# edison_mezzanine_pi_breakout.net
KiCad netlist of a schematic drawn in EAGLE
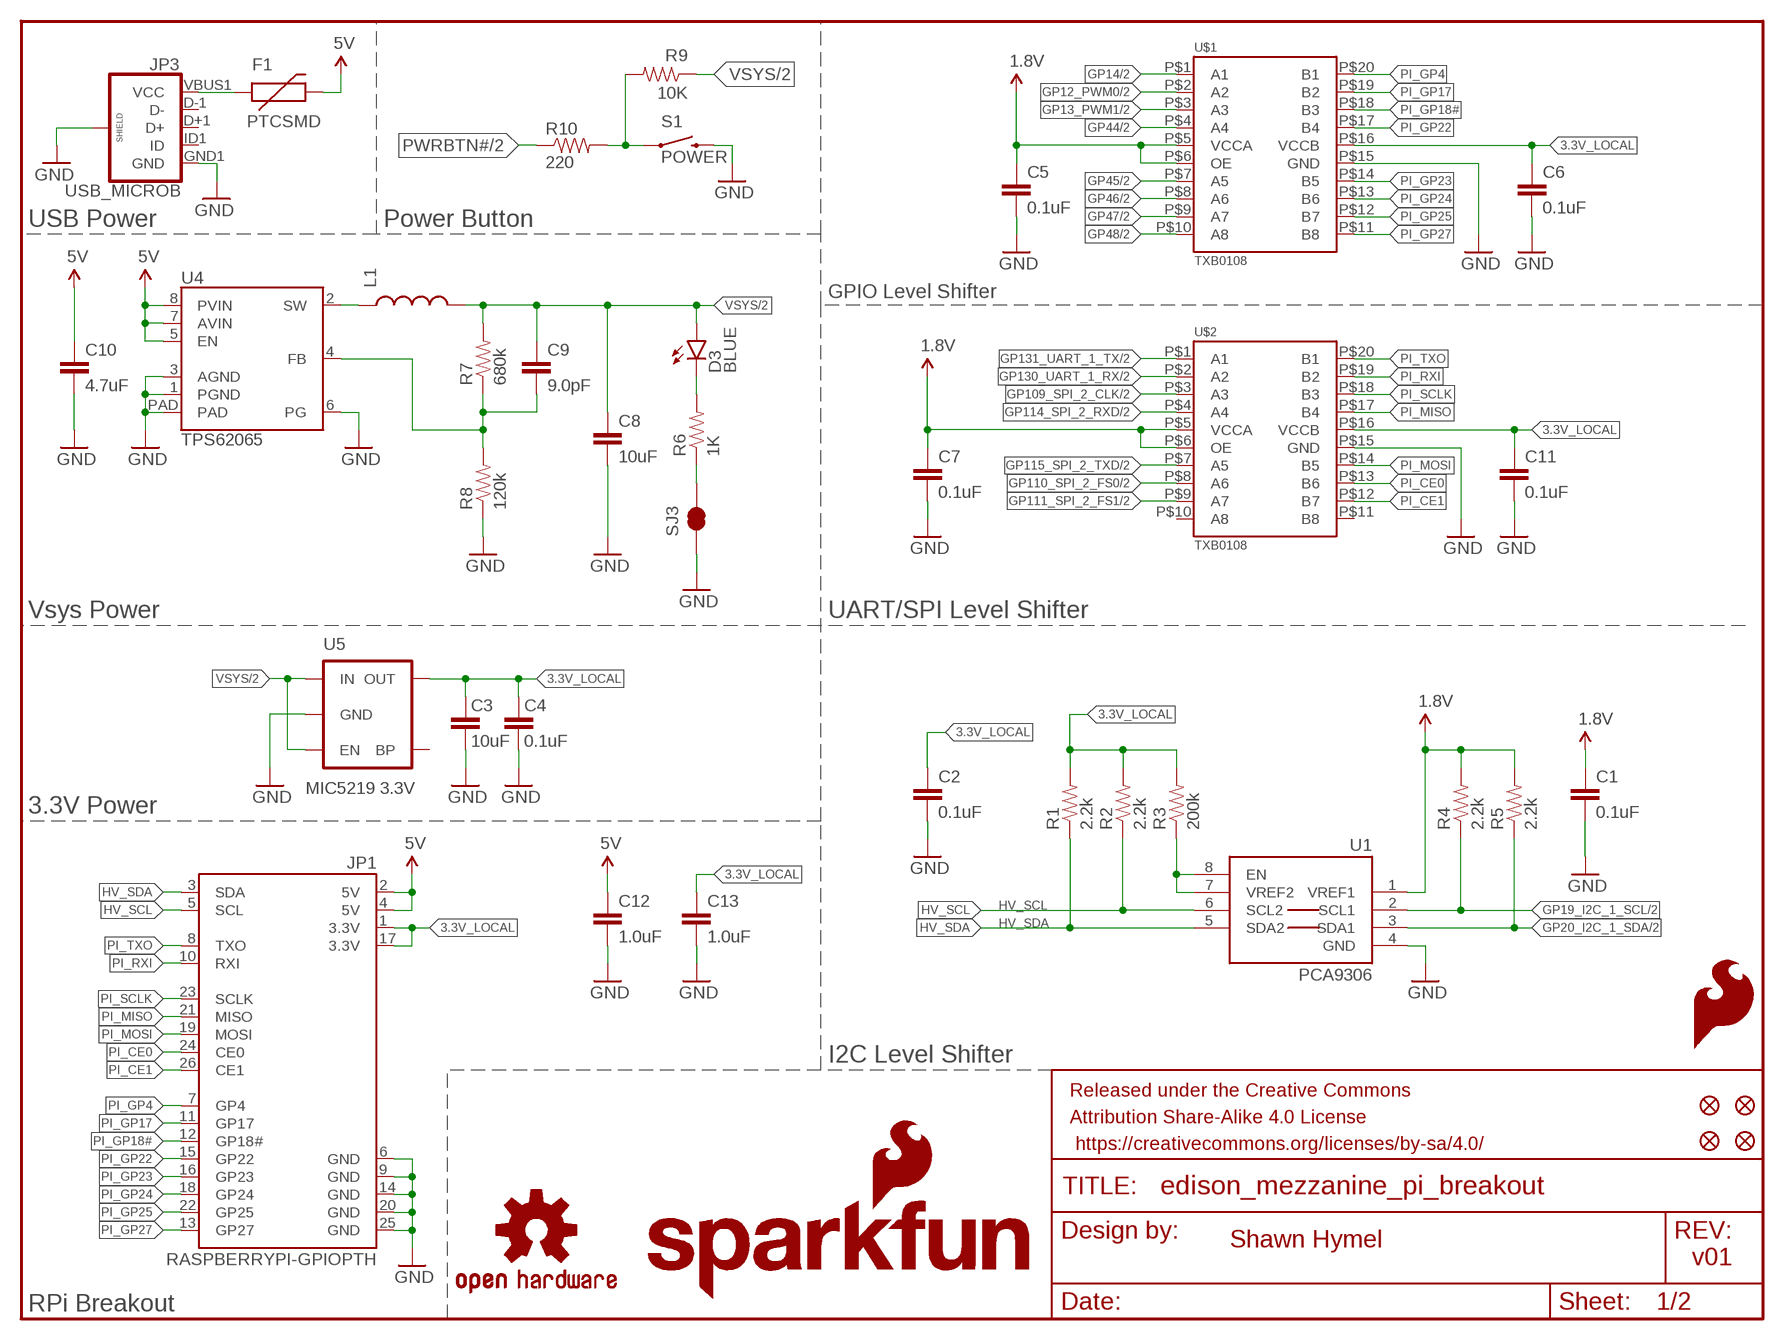
[diagram p0: schematic, sheet 1]
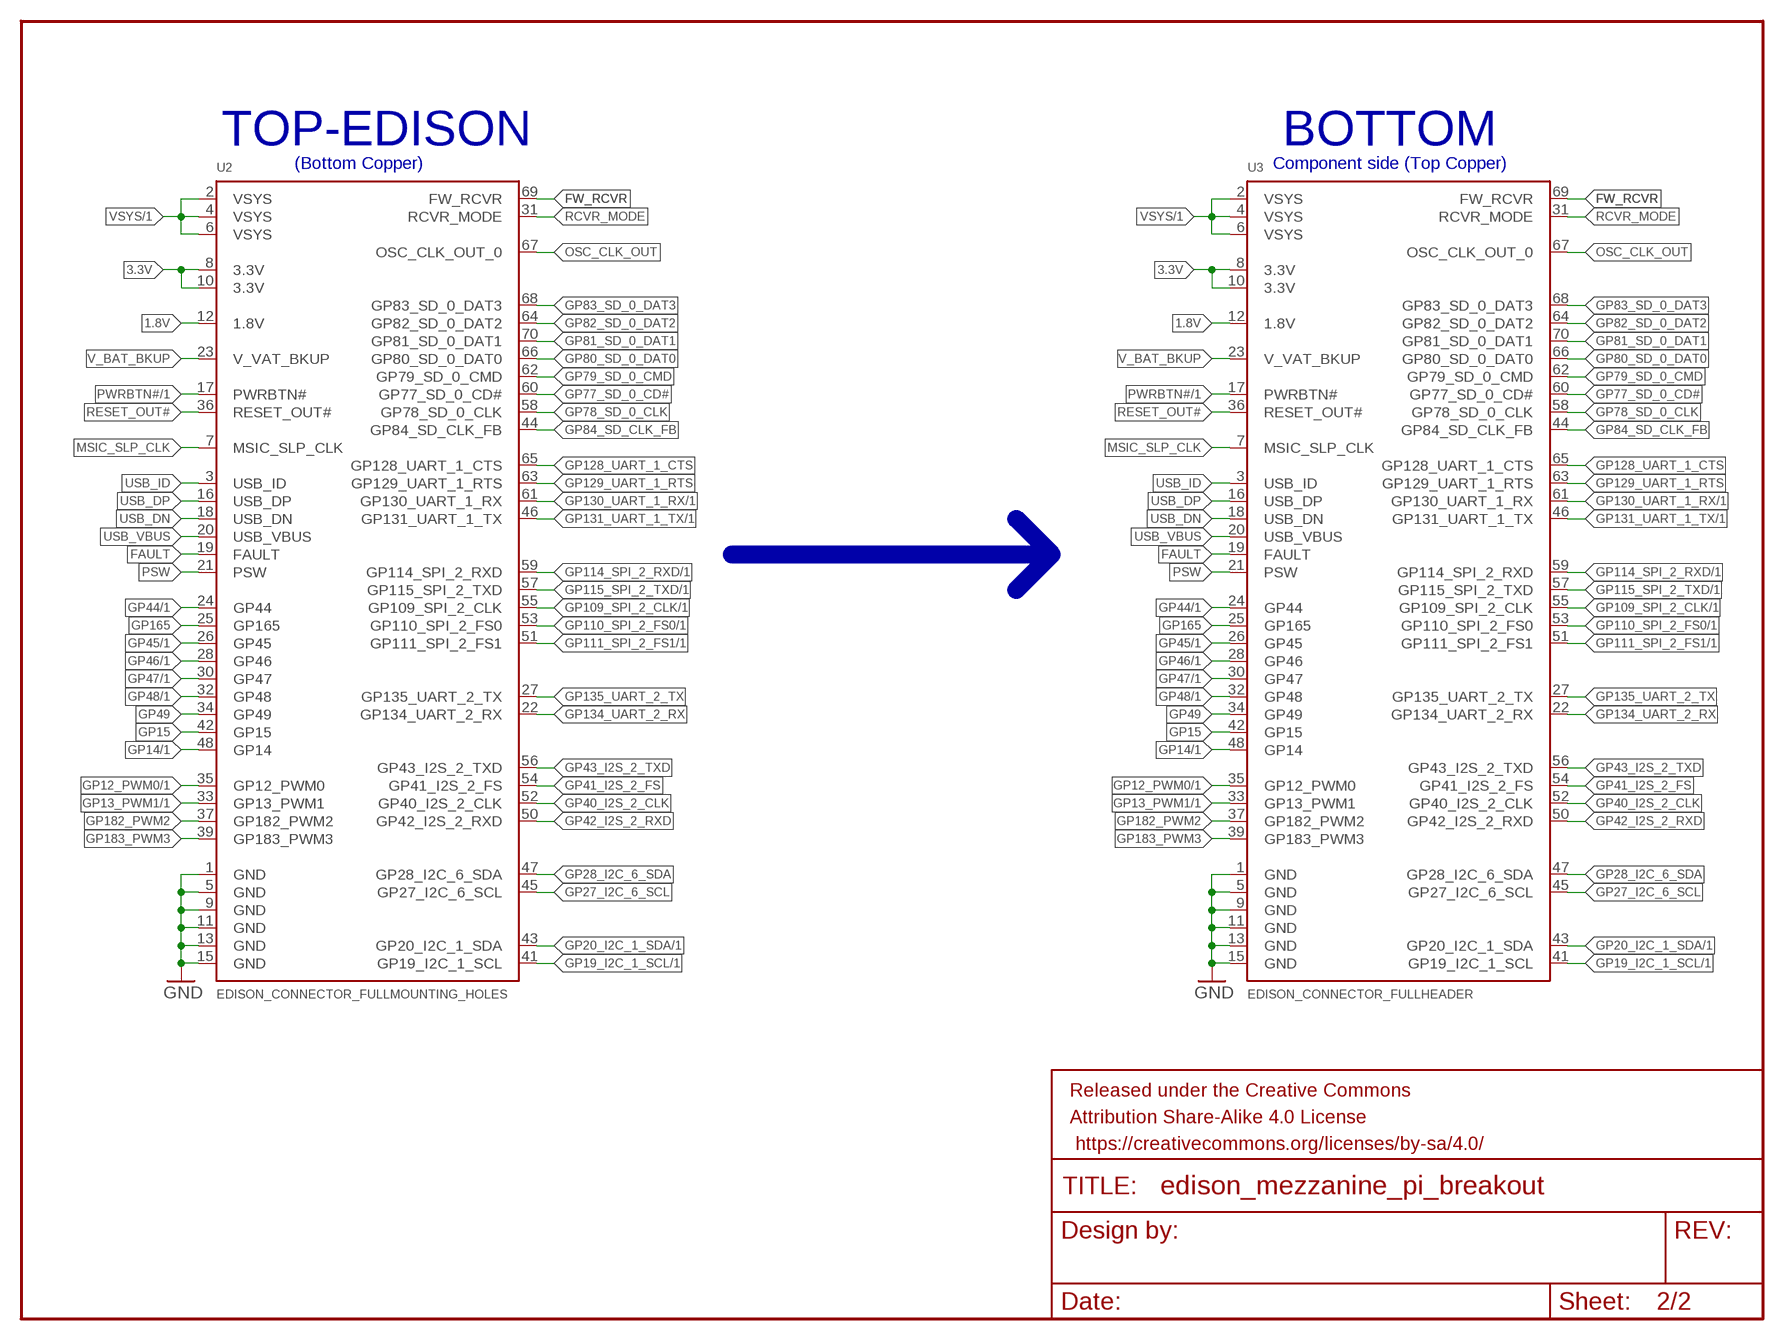
[diagram p1: schematic, sheet 2]

(export (version "E")
  (design (tool "Eeschema 10.0.6"))
  (components
    (comp (ref "FRAME2")
      (value "FRAME-LETTER")
      (footprint "eagle-import:CREATIVE_COMMONS")
      (libsource (lib "eagle-import") (part "FRAME-LETTER"))
    )
    (comp (ref "U2")
      (value "EDISON_CONNECTOR_FULLMOUNTING_HOLES")
      (footprint "eagle-import:EDISON_DAUGHTER")
      (libsource (lib "eagle-import") (part "EDISON_CONNECTOR_FULLMOUNTING_HOLES"))
    )
    (comp (ref "U3")
      (value "EDISON_CONNECTOR_FULLHEADER")
      (footprint "eagle-import:DF40C-70DP-0.4(51)")
      (libsource (lib "eagle-import") (part "EDISON_CONNECTOR_FULLHEADER"))
    )
    (comp (ref "C1")
      (value "0.1uF")
      (footprint "eagle-import:0603-CAP")
      (libsource (lib "eagle-import") (part "0.1UF-25V(+80/-20%)(0603)"))
    )
    (comp (ref "C2")
      (value "0.1uF")
      (footprint "eagle-import:0603-CAP")
      (libsource (lib "eagle-import") (part "0.1UF-25V(+80/-20%)(0603)"))
    )
    (comp (ref "C3")
      (value "10uF")
      (footprint "eagle-import:0805")
      (libsource (lib "eagle-import") (part "CAP0805"))
    )
    (comp (ref "C4")
      (value "0.1uF")
      (footprint "eagle-import:0603-CAP")
      (libsource (lib "eagle-import") (part "0.1UF-25V(+80/-20%)(0603)"))
    )
    (comp (ref "C5")
      (value "0.1uF")
      (footprint "eagle-import:0603-CAP")
      (libsource (lib "eagle-import") (part "0.1UF-25V(+80/-20%)(0603)"))
    )
    (comp (ref "C6")
      (value "0.1uF")
      (footprint "eagle-import:0603-CAP")
      (libsource (lib "eagle-import") (part "0.1UF-25V(+80/-20%)(0603)"))
    )
    (comp (ref "C7")
      (value "0.1uF")
      (footprint "eagle-import:0603-CAP")
      (libsource (lib "eagle-import") (part "0.1UF-25V(+80/-20%)(0603)"))
    )
    (comp (ref "C8")
      (value "10uF")
      (footprint "eagle-import:1206")
      (libsource (lib "eagle-import") (part "10UF-6.3V-20%(1206)"))
    )
    (comp (ref "C9")
      (value "9.0pF")
      (footprint "eagle-import:0603-CAP")
      (libsource (lib "eagle-import") (part "9.0PF-50V-10%(0603)"))
    )
    (comp (ref "C10")
      (value "4.7uF")
      (footprint "eagle-import:0603-CAP")
      (libsource (lib "eagle-import") (part "4.7UF-6.3V-10%(0603)0603"))
    )
    (comp (ref "C11")
      (value "0.1uF")
      (footprint "eagle-import:0603-CAP")
      (libsource (lib "eagle-import") (part "0.1UF-25V(+80/-20%)(0603)"))
    )
    (comp (ref "C12")
      (value "1.0uF")
      (footprint "eagle-import:0603-CAP")
      (libsource (lib "eagle-import") (part "1.0UF-16V-10%(0603)"))
    )
    (comp (ref "C13")
      (value "1.0uF")
      (footprint "eagle-import:0603-CAP")
      (libsource (lib "eagle-import") (part "1.0UF-16V-10%(0603)"))
    )
    (comp (ref "D3")
      (value "BLUE")
      (footprint "eagle-import:LED-0603")
      (libsource (lib "eagle-import") (part "LED-BLUE0603"))
    )
    (comp (ref "F1")
      (value "PTCSMD")
      (footprint "eagle-import:PTC-1206")
      (libsource (lib "eagle-import") (part "PTCSMD"))
    )
    (comp (ref "FID1")
      (value "FIDUCIAL1X2")
      (footprint "eagle-import:FIDUCIAL-1X2")
      (libsource (lib "eagle-import") (part "FIDUCIAL1X2"))
    )
    (comp (ref "FID2")
      (value "FIDUCIAL1X2")
      (footprint "eagle-import:FIDUCIAL-1X2")
      (libsource (lib "eagle-import") (part "FIDUCIAL1X2"))
    )
    (comp (ref "FID3")
      (value "FIDUCIAL1X2")
      (footprint "eagle-import:FIDUCIAL-1X2")
      (libsource (lib "eagle-import") (part "FIDUCIAL1X2"))
    )
    (comp (ref "FID4")
      (value "FIDUCIAL1X2")
      (footprint "eagle-import:FIDUCIAL-1X2")
      (libsource (lib "eagle-import") (part "FIDUCIAL1X2"))
    )
    (comp (ref "FRAME1")
      (value "FRAME-LETTER")
      (footprint "eagle-import:CREATIVE_COMMONS")
      (libsource (lib "eagle-import") (part "FRAME-LETTER"))
    )
    (comp (ref "JP1")
      (value "RASPBERRYPI-GPIOPTH")
      (footprint "eagle-import:2X13-SHROUDED")
      (libsource (lib "eagle-import") (part "RASPBERRYPI-GPIOPTH"))
    )
    (comp (ref "JP3")
      (value "USB_MICROB")
      (footprint "eagle-import:USB-B-MICRO-SMD_V03")
      (libsource (lib "eagle-import") (part "USB_MICROB_PLUGCONN-11752"))
    )
    (comp (ref "L1")
      (value "INDUCTOR")
      (footprint "eagle-import:INDUCTOR-SRP4020")
      (libsource (lib "eagle-import") (part "INDUCTOR"))
    )
    (comp (ref "LOGO1")
      (value "OSHW-LOGOS")
      (footprint "eagle-import:OSHW-LOGO-S")
      (libsource (lib "eagle-import") (part "OSHW-LOGOS"))
    )
    (comp (ref "LOGO3")
      (value "SFE_LOGO_FLAME.1_INCH")
      (footprint "eagle-import:SFE_LOGO_FLAME_.1")
      (libsource (lib "eagle-import") (part "SFE_LOGO_FLAME.1_INCH"))
    )
    (comp (ref "LOGO4")
      (value "SFE_LOGO_NAME_FLAME.1_INCH")
      (footprint "eagle-import:SFE_LOGO_NAME_FLAME_.1")
      (libsource (lib "eagle-import") (part "SFE_LOGO_NAME_FLAME.1_INCH"))
    )
    (comp (ref "R1")
      (value "2.2k")
      (footprint "eagle-import:0603-RES")
      (libsource (lib "eagle-import") (part "2.2KOHM1/10W1%(0603)"))
    )
    (comp (ref "R2")
      (value "2.2k")
      (footprint "eagle-import:0603-RES")
      (libsource (lib "eagle-import") (part "2.2KOHM1/10W1%(0603)"))
    )
    (comp (ref "R3")
      (value "200k")
      (footprint "eagle-import:0603-RES")
      (libsource (lib "eagle-import") (part "200KOHM1/10W1%(0603)200K"))
    )
    (comp (ref "R4")
      (value "2.2k")
      (footprint "eagle-import:0603-RES")
      (libsource (lib "eagle-import") (part "2.2KOHM1/10W1%(0603)"))
    )
    (comp (ref "R5")
      (value "2.2k")
      (footprint "eagle-import:0603-RES")
      (libsource (lib "eagle-import") (part "2.2KOHM1/10W1%(0603)"))
    )
    (comp (ref "R6")
      (value "1K")
      (footprint "eagle-import:0603-RES")
      (libsource (lib "eagle-import") (part "1KOHM1/10W1%(0603)"))
    )
    (comp (ref "R7")
      (value "680k")
      (footprint "eagle-import:0603-RES")
      (libsource (lib "eagle-import") (part "RESISTOR0603"))
    )
    (comp (ref "R8")
      (value "120k")
      (footprint "eagle-import:0603-RES")
      (libsource (lib "eagle-import") (part "RESISTOR0603"))
    )
    (comp (ref "R9")
      (value "10K")
      (footprint "eagle-import:0603-RES")
      (libsource (lib "eagle-import") (part "10KOHM1/10W1%(0603)0603"))
    )
    (comp (ref "R10")
      (value "220")
      (footprint "eagle-import:0603-RES")
      (libsource (lib "eagle-import") (part "RESISTOR0603"))
    )
    (comp (ref "S1")
      (value "POWER")
      (footprint "eagle-import:TACTILE-SWITCH-1101NE")
      (libsource (lib "eagle-import") (part "SWITCH-MOMENTARY-2-SMD-1101NE"))
    )
    (comp (ref "SJ3")
      (value "JUMPER-PAD-2-NC_BY_TRACE")
      (footprint "eagle-import:PAD-JUMPER-2-NC_BY_TRACE_YES_SILK")
      (libsource (lib "eagle-import") (part "JUMPER-PAD-2-NC_BY_TRACE"))
    )
    (comp (ref "U$1")
      (value "TXB0108")
      (footprint "eagle-import:UFDFN-20")
      (libsource (lib "eagle-import") (part "TXB0108"))
    )
    (comp (ref "U$2")
      (value "TXB0108")
      (footprint "eagle-import:UFDFN-20")
      (libsource (lib "eagle-import") (part "TXB0108"))
    )
    (comp (ref "U1")
      (value "PCA9306")
      (footprint "eagle-import:PCA9306DC-1_1")
      (libsource (lib "eagle-import") (part "PCA9306PCA9306DC-1{colon}1"))
    )
    (comp (ref "U4")
      (value "TPS62065")
      (footprint "eagle-import:WSON-8-PAD")
      (libsource (lib "eagle-import") (part "TPS62065"))
    )
    (comp (ref "U5")
      (value "MIC5219 3.3V")
      (footprint "eagle-import:SOT23-5")
      (libsource (lib "eagle-import") (part "V_REG_MIC52193.3V"))
    )
  )
  (nets
    (net (code "1") (name "1.8V") (class "Default")
      (node (ref "C1") (pin "1") (pinfunction "1_1") (pintype "passive"))
      (node (ref "C5") (pin "1") (pinfunction "1_1") (pintype "passive"))
      (node (ref "C7") (pin "1") (pinfunction "1_1") (pintype "passive"))
      (node (ref "R4") (pin "2") (pinfunction "2_2") (pintype "passive"))
      (node (ref "R5") (pin "2") (pinfunction "2_2") (pintype "passive"))
      (node (ref "U$1") (pin "P$5") (pinfunction "VCCA_P$5") (pintype "bidirectional"))
      (node (ref "U$1") (pin "P$6") (pinfunction "OE_P$6") (pintype "bidirectional"))
      (node (ref "U$2") (pin "P$5") (pinfunction "VCCA_P$5") (pintype "bidirectional"))
      (node (ref "U$2") (pin "P$6") (pinfunction "OE_P$6") (pintype "bidirectional"))
      (node (ref "U1") (pin "1") (pinfunction "VREF1_1") (pintype "bidirectional"))
      (node (ref "U2") (pin "12") (pinfunction "1.8V_12") (pintype "bidirectional"))
      (node (ref "U3") (pin "12") (pinfunction "1.8V_12") (pintype "bidirectional"))
    )
    (net (code "2") (name "3.3V") (class "Default")
      (node (ref "U2") (pin "10") (pinfunction "3.3V_10") (pintype "bidirectional"))
      (node (ref "U2") (pin "8") (pinfunction "3.3V_8") (pintype "bidirectional"))
      (node (ref "U3") (pin "10") (pinfunction "3.3V_10") (pintype "bidirectional"))
      (node (ref "U3") (pin "8") (pinfunction "3.3V_8") (pintype "bidirectional"))
    )
    (net (code "3") (name "3.3V_LOCAL") (class "Default")
      (node (ref "C11") (pin "1") (pinfunction "1_1") (pintype "passive"))
      (node (ref "C13") (pin "1") (pinfunction "1_1") (pintype "passive"))
      (node (ref "C2") (pin "1") (pinfunction "1_1") (pintype "passive"))
      (node (ref "C3") (pin "1") (pinfunction "1_1") (pintype "passive"))
      (node (ref "C4") (pin "1") (pinfunction "1_1") (pintype "passive"))
      (node (ref "C6") (pin "1") (pinfunction "1_1") (pintype "passive"))
      (node (ref "JP1") (pin "1") (pinfunction "3.3V_1") (pintype "power_in"))
      (node (ref "JP1") (pin "17") (pinfunction "3.3V_17") (pintype "power_in"))
      (node (ref "R1") (pin "2") (pinfunction "2_2") (pintype "passive"))
      (node (ref "R2") (pin "2") (pinfunction "2_2") (pintype "passive"))
      (node (ref "R3") (pin "2") (pinfunction "2_2") (pintype "passive"))
      (node (ref "U$1") (pin "P$16") (pinfunction "VCCB_P$16") (pintype "bidirectional"))
      (node (ref "U$2") (pin "P$16") (pinfunction "VCCB_P$16") (pintype "bidirectional"))
      (node (ref "U5") (pin "5") (pinfunction "OUT_5") (pintype "passive"))
    )
    (net (code "4") (name "5V") (class "Default")
      (node (ref "C10") (pin "1") (pinfunction "1_1") (pintype "passive"))
      (node (ref "C12") (pin "1") (pinfunction "1_1") (pintype "passive"))
      (node (ref "F1") (pin "2") (pinfunction "2_2") (pintype "bidirectional"))
      (node (ref "JP1") (pin "2") (pinfunction "5V_2") (pintype "power_in"))
      (node (ref "JP1") (pin "4") (pinfunction "5V_4") (pintype "power_in"))
      (node (ref "U4") (pin "5") (pinfunction "EN_5") (pintype "bidirectional"))
      (node (ref "U4") (pin "7") (pinfunction "AVIN_7") (pintype "bidirectional"))
      (node (ref "U4") (pin "8") (pinfunction "PVIN_8") (pintype "bidirectional"))
    )
    (net (code "5") (name "FAULT") (class "Default")
      (node (ref "U2") (pin "19") (pinfunction "FAULT_19") (pintype "bidirectional"))
      (node (ref "U3") (pin "19") (pinfunction "FAULT_19") (pintype "bidirectional"))
    )
    (net (code "6") (name "FW_RCVR") (class "Default")
      (node (ref "U2") (pin "69") (pinfunction "FW_RCVR_69") (pintype "bidirectional"))
      (node (ref "U3") (pin "69") (pinfunction "FW_RCVR_69") (pintype "bidirectional"))
    )
    (net (code "7") (name "GND") (class "Default")
      (node (ref "C1") (pin "2") (pinfunction "2_2") (pintype "passive"))
      (node (ref "C10") (pin "2") (pinfunction "2_2") (pintype "passive"))
      (node (ref "C11") (pin "2") (pinfunction "2_2") (pintype "passive"))
      (node (ref "C12") (pin "2") (pinfunction "2_2") (pintype "passive"))
      (node (ref "C13") (pin "2") (pinfunction "2_2") (pintype "passive"))
      (node (ref "C2") (pin "2") (pinfunction "2_2") (pintype "passive"))
      (node (ref "C3") (pin "2") (pinfunction "2_2") (pintype "passive"))
      (node (ref "C4") (pin "2") (pinfunction "2_2") (pintype "passive"))
      (node (ref "C5") (pin "2") (pinfunction "2_2") (pintype "passive"))
      (node (ref "C6") (pin "2") (pinfunction "2_2") (pintype "passive"))
      (node (ref "C7") (pin "2") (pinfunction "2_2") (pintype "passive"))
      (node (ref "C8") (pin "2") (pinfunction "2_2") (pintype "passive"))
      (node (ref "JP1") (pin "14") (pinfunction "GND_14") (pintype "power_in"))
      (node (ref "JP1") (pin "20") (pinfunction "GND_20") (pintype "power_in"))
      (node (ref "JP1") (pin "25") (pinfunction "GND_25") (pintype "power_in"))
      (node (ref "JP1") (pin "6") (pinfunction "GND_6") (pintype "power_in"))
      (node (ref "JP1") (pin "9") (pinfunction "GND_9") (pintype "power_in"))
      (node (ref "JP3") (pin "GND1") (pinfunction "GND_GND1") (pintype "bidirectional"))
      (node (ref "JP3") (pin "SHIELD1") (pinfunction "SHIELD_SHIELD1") (pintype "bidirectional"))
      (node (ref "JP3") (pin "SHIELD2") (pinfunction "SHIELD_SHIELD2") (pintype "bidirectional"))
      (node (ref "JP3") (pin "SHIELD3") (pinfunction "SHIELD_SHIELD3") (pintype "bidirectional"))
      (node (ref "R8") (pin "1") (pinfunction "1_1") (pintype "passive"))
      (node (ref "S1") (pin "P$2") (pinfunction "2_P$2") (pintype "passive"))
      (node (ref "SJ3") (pin "1") (pinfunction "1_1") (pintype "passive"))
      (node (ref "U$1") (pin "P$15") (pinfunction "GND_P$15") (pintype "bidirectional"))
      (node (ref "U$2") (pin "P$15") (pinfunction "GND_P$15") (pintype "bidirectional"))
      (node (ref "U1") (pin "4") (pinfunction "GND_4") (pintype "bidirectional"))
      (node (ref "U2") (pin "1") (pinfunction "GND_1") (pintype "bidirectional"))
      (node (ref "U2") (pin "11") (pinfunction "GND_11") (pintype "bidirectional"))
      (node (ref "U2") (pin "13") (pinfunction "GND_13") (pintype "bidirectional"))
      (node (ref "U2") (pin "15") (pinfunction "GND_15") (pintype "bidirectional"))
      (node (ref "U2") (pin "5") (pinfunction "GND_5") (pintype "bidirectional"))
      (node (ref "U2") (pin "9") (pinfunction "GND_9") (pintype "bidirectional"))
      (node (ref "U3") (pin "1") (pinfunction "GND_1") (pintype "bidirectional"))
      (node (ref "U3") (pin "11") (pinfunction "GND_11") (pintype "bidirectional"))
      (node (ref "U3") (pin "13") (pinfunction "GND_13") (pintype "bidirectional"))
      (node (ref "U3") (pin "15") (pinfunction "GND_15") (pintype "bidirectional"))
      (node (ref "U3") (pin "5") (pinfunction "GND_5") (pintype "bidirectional"))
      (node (ref "U3") (pin "9") (pinfunction "GND_9") (pintype "bidirectional"))
      (node (ref "U4") (pin "1") (pinfunction "PGND_1") (pintype "bidirectional"))
      (node (ref "U4") (pin "3") (pinfunction "AGND_3") (pintype "bidirectional"))
      (node (ref "U4") (pin "6") (pinfunction "PG_6") (pintype "bidirectional"))
      (node (ref "U4") (pin "PAD") (pinfunction "PAD_PAD") (pintype "bidirectional"))
      (node (ref "U5") (pin "2") (pinfunction "GND_2") (pintype "input"))
    )
    (net (code "8") (name "GP12_PWM0") (class "Default")
      (node (ref "U$1") (pin "P$2") (pinfunction "A2_P$2") (pintype "bidirectional"))
      (node (ref "U2") (pin "35") (pinfunction "GP12_PWM0_35") (pintype "bidirectional"))
      (node (ref "U3") (pin "35") (pinfunction "GP12_PWM0_35") (pintype "bidirectional"))
    )
    (net (code "9") (name "GP13_PWM1") (class "Default")
      (node (ref "U$1") (pin "P$3") (pinfunction "A3_P$3") (pintype "bidirectional"))
      (node (ref "U2") (pin "33") (pinfunction "GP13_PWM1_33") (pintype "bidirectional"))
      (node (ref "U3") (pin "33") (pinfunction "GP13_PWM1_33") (pintype "bidirectional"))
    )
    (net (code "10") (name "GP14") (class "Default")
      (node (ref "U$1") (pin "P$1") (pinfunction "A1_P$1") (pintype "bidirectional"))
      (node (ref "U2") (pin "48") (pinfunction "GP14_48") (pintype "bidirectional"))
      (node (ref "U3") (pin "48") (pinfunction "GP14_48") (pintype "bidirectional"))
    )
    (net (code "11") (name "GP15") (class "Default")
      (node (ref "U2") (pin "42") (pinfunction "GP15_42") (pintype "bidirectional"))
      (node (ref "U3") (pin "42") (pinfunction "GP15_42") (pintype "bidirectional"))
    )
    (net (code "12") (name "GP19_I2C_1_SCL") (class "Default")
      (node (ref "R4") (pin "1") (pinfunction "1_1") (pintype "passive"))
      (node (ref "U1") (pin "2") (pinfunction "SCL1_2") (pintype "bidirectional"))
      (node (ref "U2") (pin "41") (pinfunction "GP19_I2C_1_SCL_41") (pintype "bidirectional"))
      (node (ref "U3") (pin "41") (pinfunction "GP19_I2C_1_SCL_41") (pintype "bidirectional"))
    )
    (net (code "13") (name "GP20_I2C_1_SDA") (class "Default")
      (node (ref "R5") (pin "1") (pinfunction "1_1") (pintype "passive"))
      (node (ref "U1") (pin "3") (pinfunction "SDA1_3") (pintype "bidirectional"))
      (node (ref "U2") (pin "43") (pinfunction "GP20_I2C_1_SDA_43") (pintype "bidirectional"))
      (node (ref "U3") (pin "43") (pinfunction "GP20_I2C_1_SDA_43") (pintype "bidirectional"))
    )
    (net (code "14") (name "GP27_I2C_6_SCL") (class "Default")
      (node (ref "U2") (pin "45") (pinfunction "GP27_I2C_6_SCL_45") (pintype "bidirectional"))
      (node (ref "U3") (pin "45") (pinfunction "GP27_I2C_6_SCL_45") (pintype "bidirectional"))
    )
    (net (code "15") (name "GP28_I2C_6_SDA") (class "Default")
      (node (ref "U2") (pin "47") (pinfunction "GP28_I2C_6_SDA_47") (pintype "bidirectional"))
      (node (ref "U3") (pin "47") (pinfunction "GP28_I2C_6_SDA_47") (pintype "bidirectional"))
    )
    (net (code "16") (name "GP40_I2S_2_CLK") (class "Default")
      (node (ref "U2") (pin "52") (pinfunction "GP40_I2S_2_CLK_52") (pintype "bidirectional"))
      (node (ref "U3") (pin "52") (pinfunction "GP40_I2S_2_CLK_52") (pintype "bidirectional"))
    )
    (net (code "17") (name "GP41_I2S_2_FS") (class "Default")
      (node (ref "U2") (pin "54") (pinfunction "GP41_I2S_2_FS_54") (pintype "bidirectional"))
      (node (ref "U3") (pin "54") (pinfunction "GP41_I2S_2_FS_54") (pintype "bidirectional"))
    )
    (net (code "18") (name "GP42_I2S_2_RXD") (class "Default")
      (node (ref "U2") (pin "50") (pinfunction "GP42_I2S_2_RXD_50") (pintype "bidirectional"))
      (node (ref "U3") (pin "50") (pinfunction "GP42_I2S_2_RXD_50") (pintype "bidirectional"))
    )
    (net (code "19") (name "GP43_I2S_2_TXD") (class "Default")
      (node (ref "U2") (pin "56") (pinfunction "GP43_I2S_2_TXD_56") (pintype "bidirectional"))
      (node (ref "U3") (pin "56") (pinfunction "GP43_I2S_2_TXD_56") (pintype "bidirectional"))
    )
    (net (code "20") (name "GP44") (class "Default")
      (node (ref "U$1") (pin "P$4") (pinfunction "A4_P$4") (pintype "bidirectional"))
      (node (ref "U2") (pin "24") (pinfunction "GP44_24") (pintype "bidirectional"))
      (node (ref "U3") (pin "24") (pinfunction "GP44_24") (pintype "bidirectional"))
    )
    (net (code "21") (name "GP45") (class "Default")
      (node (ref "U$1") (pin "P$7") (pinfunction "A5_P$7") (pintype "bidirectional"))
      (node (ref "U2") (pin "26") (pinfunction "GP45_26") (pintype "bidirectional"))
      (node (ref "U3") (pin "26") (pinfunction "GP45_26") (pintype "bidirectional"))
    )
    (net (code "22") (name "GP46") (class "Default")
      (node (ref "U$1") (pin "P$8") (pinfunction "A6_P$8") (pintype "bidirectional"))
      (node (ref "U2") (pin "28") (pinfunction "GP46_28") (pintype "bidirectional"))
      (node (ref "U3") (pin "28") (pinfunction "GP46_28") (pintype "bidirectional"))
    )
    (net (code "23") (name "GP47") (class "Default")
      (node (ref "U$1") (pin "P$9") (pinfunction "A7_P$9") (pintype "bidirectional"))
      (node (ref "U2") (pin "30") (pinfunction "GP47_30") (pintype "bidirectional"))
      (node (ref "U3") (pin "30") (pinfunction "GP47_30") (pintype "bidirectional"))
    )
    (net (code "24") (name "GP48") (class "Default")
      (node (ref "U$1") (pin "P$10") (pinfunction "A8_P$10") (pintype "bidirectional"))
      (node (ref "U2") (pin "32") (pinfunction "GP48_32") (pintype "bidirectional"))
      (node (ref "U3") (pin "32") (pinfunction "GP48_32") (pintype "bidirectional"))
    )
    (net (code "25") (name "GP49") (class "Default")
      (node (ref "U2") (pin "34") (pinfunction "GP49_34") (pintype "bidirectional"))
      (node (ref "U3") (pin "34") (pinfunction "GP49_34") (pintype "bidirectional"))
    )
    (net (code "26") (name "GP77_SD_0_CD#") (class "Default")
      (node (ref "U2") (pin "60") (pinfunction "GP77_SD_0_CD#_60") (pintype "bidirectional"))
      (node (ref "U3") (pin "60") (pinfunction "GP77_SD_0_CD#_60") (pintype "bidirectional"))
    )
    (net (code "27") (name "GP78_SD_0_CLK") (class "Default")
      (node (ref "U2") (pin "58") (pinfunction "GP78_SD_0_CLK_58") (pintype "bidirectional"))
      (node (ref "U3") (pin "58") (pinfunction "GP78_SD_0_CLK_58") (pintype "bidirectional"))
    )
    (net (code "28") (name "GP79_SD_0_CMD") (class "Default")
      (node (ref "U2") (pin "62") (pinfunction "GP79_SD_0_CMD_62") (pintype "bidirectional"))
      (node (ref "U3") (pin "62") (pinfunction "GP79_SD_0_CMD_62") (pintype "bidirectional"))
    )
    (net (code "29") (name "GP80_SD_0_DAT0") (class "Default")
      (node (ref "U2") (pin "66") (pinfunction "GP80_SD_0_DAT0_66") (pintype "bidirectional"))
      (node (ref "U3") (pin "66") (pinfunction "GP80_SD_0_DAT0_66") (pintype "bidirectional"))
    )
    (net (code "30") (name "GP81_SD_0_DAT1") (class "Default")
      (node (ref "U2") (pin "70") (pinfunction "GP81_SD_0_DAT1_70") (pintype "bidirectional"))
      (node (ref "U3") (pin "70") (pinfunction "GP81_SD_0_DAT1_70") (pintype "bidirectional"))
    )
    (net (code "31") (name "GP82_SD_0_DAT2") (class "Default")
      (node (ref "U2") (pin "64") (pinfunction "GP82_SD_0_DAT2_64") (pintype "bidirectional"))
      (node (ref "U3") (pin "64") (pinfunction "GP82_SD_0_DAT2_64") (pintype "bidirectional"))
    )
    (net (code "32") (name "GP83_SD_0_DAT3") (class "Default")
      (node (ref "U2") (pin "68") (pinfunction "GP83_SD_0_DAT3_68") (pintype "bidirectional"))
      (node (ref "U3") (pin "68") (pinfunction "GP83_SD_0_DAT3_68") (pintype "bidirectional"))
    )
    (net (code "33") (name "GP84_SD_CLK_FB") (class "Default")
      (node (ref "U2") (pin "44") (pinfunction "GP84_SD_CLK_FB_44") (pintype "bidirectional"))
      (node (ref "U3") (pin "44") (pinfunction "GP84_SD_CLK_FB_44") (pintype "bidirectional"))
    )
    (net (code "34") (name "GP109_SPI_2_CLK") (class "Default")
      (node (ref "U$2") (pin "P$3") (pinfunction "A3_P$3") (pintype "bidirectional"))
      (node (ref "U2") (pin "55") (pinfunction "GP109_SPI_2_CLK_55") (pintype "bidirectional"))
      (node (ref "U3") (pin "55") (pinfunction "GP109_SPI_2_CLK_55") (pintype "bidirectional"))
    )
    (net (code "35") (name "GP110_SPI_2_FS0") (class "Default")
      (node (ref "U$2") (pin "P$8") (pinfunction "A6_P$8") (pintype "bidirectional"))
      (node (ref "U2") (pin "53") (pinfunction "GP110_SPI_2_FS0_53") (pintype "bidirectional"))
      (node (ref "U3") (pin "53") (pinfunction "GP110_SPI_2_FS0_53") (pintype "bidirectional"))
    )
    (net (code "36") (name "GP111_SPI_2_FS1") (class "Default")
      (node (ref "U$2") (pin "P$9") (pinfunction "A7_P$9") (pintype "bidirectional"))
      (node (ref "U2") (pin "51") (pinfunction "GP111_SPI_2_FS1_51") (pintype "bidirectional"))
      (node (ref "U3") (pin "51") (pinfunction "GP111_SPI_2_FS1_51") (pintype "bidirectional"))
    )
    (net (code "37") (name "GP114_SPI_2_RXD") (class "Default")
      (node (ref "U$2") (pin "P$4") (pinfunction "A4_P$4") (pintype "bidirectional"))
      (node (ref "U2") (pin "59") (pinfunction "GP114_SPI_2_RXD_59") (pintype "bidirectional"))
      (node (ref "U3") (pin "59") (pinfunction "GP114_SPI_2_RXD_59") (pintype "bidirectional"))
    )
    (net (code "38") (name "GP115_SPI_2_TXD") (class "Default")
      (node (ref "U$2") (pin "P$7") (pinfunction "A5_P$7") (pintype "bidirectional"))
      (node (ref "U2") (pin "57") (pinfunction "GP115_SPI_2_TXD_57") (pintype "bidirectional"))
      (node (ref "U3") (pin "57") (pinfunction "GP115_SPI_2_TXD_57") (pintype "bidirectional"))
    )
    (net (code "39") (name "GP128_UART_1_CTS") (class "Default")
      (node (ref "U2") (pin "65") (pinfunction "GP128_UART_1_CTS_65") (pintype "bidirectional"))
      (node (ref "U3") (pin "65") (pinfunction "GP128_UART_1_CTS_65") (pintype "bidirectional"))
    )
    (net (code "40") (name "GP129_UART_1_RTS") (class "Default")
      (node (ref "U2") (pin "63") (pinfunction "GP129_UART_1_RTS_63") (pintype "bidirectional"))
      (node (ref "U3") (pin "63") (pinfunction "GP129_UART_1_RTS_63") (pintype "bidirectional"))
    )
    (net (code "41") (name "GP130_UART_1_RX") (class "Default")
      (node (ref "U$2") (pin "P$2") (pinfunction "A2_P$2") (pintype "bidirectional"))
      (node (ref "U2") (pin "61") (pinfunction "GP130_UART_1_RX_61") (pintype "bidirectional"))
      (node (ref "U3") (pin "61") (pinfunction "GP130_UART_1_RX_61") (pintype "bidirectional"))
    )
    (net (code "42") (name "GP131_UART_1_TX") (class "Default")
      (node (ref "U$2") (pin "P$1") (pinfunction "A1_P$1") (pintype "bidirectional"))
      (node (ref "U2") (pin "46") (pinfunction "GP131_UART_1_TX_46") (pintype "bidirectional"))
      (node (ref "U3") (pin "46") (pinfunction "GP131_UART_1_TX_46") (pintype "bidirectional"))
    )
    (net (code "43") (name "GP134_UART_2_RX") (class "Default")
      (node (ref "U2") (pin "22") (pinfunction "GP134_UART_2_RX_22") (pintype "bidirectional"))
      (node (ref "U3") (pin "22") (pinfunction "GP134_UART_2_RX_22") (pintype "bidirectional"))
    )
    (net (code "44") (name "GP135_UART_2_TX") (class "Default")
      (node (ref "U2") (pin "27") (pinfunction "GP135_UART_2_TX_27") (pintype "bidirectional"))
      (node (ref "U3") (pin "27") (pinfunction "GP135_UART_2_TX_27") (pintype "bidirectional"))
    )
    (net (code "45") (name "GP165") (class "Default")
      (node (ref "U2") (pin "25") (pinfunction "GP165_25") (pintype "bidirectional"))
      (node (ref "U3") (pin "25") (pinfunction "GP165_25") (pintype "bidirectional"))
    )
    (net (code "46") (name "GP182_PWM2") (class "Default")
      (node (ref "U2") (pin "37") (pinfunction "GP182_PWM2_37") (pintype "bidirectional"))
      (node (ref "U3") (pin "37") (pinfunction "GP182_PWM2_37") (pintype "bidirectional"))
    )
    (net (code "47") (name "GP183_PWM3") (class "Default")
      (node (ref "U2") (pin "39") (pinfunction "GP183_PWM3_39") (pintype "bidirectional"))
      (node (ref "U3") (pin "39") (pinfunction "GP183_PWM3_39") (pintype "bidirectional"))
    )
    (net (code "48") (name "HV_SCL") (class "Default")
      (node (ref "JP1") (pin "5") (pinfunction "SCL_5") (pintype "bidirectional"))
      (node (ref "R2") (pin "1") (pinfunction "1_1") (pintype "passive"))
      (node (ref "U1") (pin "6") (pinfunction "SCL2_6") (pintype "bidirectional"))
    )
    (net (code "49") (name "HV_SDA") (class "Default")
      (node (ref "JP1") (pin "3") (pinfunction "SDA_3") (pintype "bidirectional"))
      (node (ref "R1") (pin "1") (pinfunction "1_1") (pintype "passive"))
      (node (ref "U1") (pin "5") (pinfunction "SDA2_5") (pintype "bidirectional"))
    )
    (net (code "50") (name "MSIC_SLP_CLK") (class "Default")
      (node (ref "U2") (pin "7") (pinfunction "MSIC_SLP_CLK_7") (pintype "bidirectional"))
      (node (ref "U3") (pin "7") (pinfunction "MSIC_SLP_CLK_7") (pintype "bidirectional"))
    )
    (net (code "51") (name "Net-(D3-PadC)") (class "Default")
      (node (ref "D3") (pin "C") (pinfunction "C_C") (pintype "passive"))
      (node (ref "R6") (pin "2") (pinfunction "2_2") (pintype "passive"))
    )
    (net (code "52") (name "Net-(JP3-VCC)") (class "Default")
      (node (ref "F1") (pin "1") (pinfunction "1_1") (pintype "bidirectional"))
      (node (ref "JP3") (pin "VBUS1") (pinfunction "VCC_VBUS1") (pintype "bidirectional"))
    )
    (net (code "53") (name "Net-(L1-1)") (class "Default")
      (node (ref "L1") (pin "P$1") (pinfunction "1_P$1") (pintype "passive"))
      (node (ref "U4") (pin "2") (pinfunction "SW_2") (pintype "bidirectional"))
    )
    (net (code "54") (name "Net-(R6-Pad1)") (class "Default")
      (node (ref "R6") (pin "1") (pinfunction "1_1") (pintype "passive"))
      (node (ref "SJ3") (pin "2") (pinfunction "2_2") (pintype "passive"))
    )
    (net (code "55") (name "Net-(S1-1)") (class "Default")
      (node (ref "R10") (pin "2") (pinfunction "2_2") (pintype "passive"))
      (node (ref "R9") (pin "2") (pinfunction "2_2") (pintype "passive"))
      (node (ref "S1") (pin "P$1") (pinfunction "1_P$1") (pintype "passive"))
    )
    (net (code "56") (name "Net-(U1-EN)") (class "Default")
      (node (ref "R3") (pin "1") (pinfunction "1_1") (pintype "passive"))
      (node (ref "U1") (pin "7") (pinfunction "VREF2_7") (pintype "bidirectional"))
      (node (ref "U1") (pin "8") (pinfunction "EN_8") (pintype "bidirectional"))
    )
    (net (code "57") (name "Net-(U4-FB)") (class "Default")
      (node (ref "C9") (pin "2") (pinfunction "2_2") (pintype "passive"))
      (node (ref "R7") (pin "1") (pinfunction "1_1") (pintype "passive"))
      (node (ref "R8") (pin "2") (pinfunction "2_2") (pintype "passive"))
      (node (ref "U4") (pin "4") (pinfunction "FB_4") (pintype "bidirectional"))
    )
    (net (code "58") (name "OSC_CLK_OUT") (class "Default")
      (node (ref "U2") (pin "67") (pinfunction "OSC_CLK_OUT_0_67") (pintype "bidirectional"))
      (node (ref "U3") (pin "67") (pinfunction "OSC_CLK_OUT_0_67") (pintype "bidirectional"))
    )
    (net (code "59") (name "PI_CE0") (class "Default")
      (node (ref "JP1") (pin "24") (pinfunction "CE0_24") (pintype "output"))
      (node (ref "U$2") (pin "P$13") (pinfunction "B6_P$13") (pintype "bidirectional"))
    )
    (net (code "60") (name "PI_CE1") (class "Default")
      (node (ref "JP1") (pin "26") (pinfunction "CE1_26") (pintype "output"))
      (node (ref "U$2") (pin "P$12") (pinfunction "B7_P$12") (pintype "bidirectional"))
    )
    (net (code "61") (name "PI_GP4") (class "Default")
      (node (ref "JP1") (pin "7") (pinfunction "GP4_7") (pintype "bidirectional"))
      (node (ref "U$1") (pin "P$20") (pinfunction "B1_P$20") (pintype "bidirectional"))
    )
    (net (code "62") (name "PI_GP17") (class "Default")
      (node (ref "JP1") (pin "11") (pinfunction "GP17_11") (pintype "bidirectional"))
      (node (ref "U$1") (pin "P$19") (pinfunction "B2_P$19") (pintype "bidirectional"))
    )
    (net (code "63") (name "PI_GP18#") (class "Default")
      (node (ref "JP1") (pin "12") (pinfunction "GP18#_12") (pintype "bidirectional"))
      (node (ref "U$1") (pin "P$18") (pinfunction "B3_P$18") (pintype "bidirectional"))
    )
    (net (code "64") (name "PI_GP22") (class "Default")
      (node (ref "JP1") (pin "15") (pinfunction "GP22_15") (pintype "bidirectional"))
      (node (ref "U$1") (pin "P$17") (pinfunction "B4_P$17") (pintype "bidirectional"))
    )
    (net (code "65") (name "PI_GP23") (class "Default")
      (node (ref "JP1") (pin "16") (pinfunction "GP23_16") (pintype "bidirectional"))
      (node (ref "U$1") (pin "P$14") (pinfunction "B5_P$14") (pintype "bidirectional"))
    )
    (net (code "66") (name "PI_GP24") (class "Default")
      (node (ref "JP1") (pin "18") (pinfunction "GP24_18") (pintype "bidirectional"))
      (node (ref "U$1") (pin "P$13") (pinfunction "B6_P$13") (pintype "bidirectional"))
    )
    (net (code "67") (name "PI_GP25") (class "Default")
      (node (ref "JP1") (pin "22") (pinfunction "GP25_22") (pintype "bidirectional"))
      (node (ref "U$1") (pin "P$12") (pinfunction "B7_P$12") (pintype "bidirectional"))
    )
    (net (code "68") (name "PI_GP27") (class "Default")
      (node (ref "JP1") (pin "13") (pinfunction "GP27_13") (pintype "bidirectional"))
      (node (ref "U$1") (pin "P$11") (pinfunction "B8_P$11") (pintype "bidirectional"))
    )
    (net (code "69") (name "PI_MISO") (class "Default")
      (node (ref "JP1") (pin "21") (pinfunction "MISO_21") (pintype "input"))
      (node (ref "U$2") (pin "P$17") (pinfunction "B4_P$17") (pintype "bidirectional"))
    )
    (net (code "70") (name "PI_MOSI") (class "Default")
      (node (ref "JP1") (pin "19") (pinfunction "MOSI_19") (pintype "output"))
      (node (ref "U$2") (pin "P$14") (pinfunction "B5_P$14") (pintype "bidirectional"))
    )
    (net (code "71") (name "PI_RXI") (class "Default")
      (node (ref "JP1") (pin "10") (pinfunction "RXI_10") (pintype "input"))
      (node (ref "U$2") (pin "P$19") (pinfunction "B2_P$19") (pintype "bidirectional"))
    )
    (net (code "72") (name "PI_SCLK") (class "Default")
      (node (ref "JP1") (pin "23") (pinfunction "SCLK_23") (pintype "output"))
      (node (ref "U$2") (pin "P$18") (pinfunction "B3_P$18") (pintype "bidirectional"))
    )
    (net (code "73") (name "PI_TXO") (class "Default")
      (node (ref "JP1") (pin "8") (pinfunction "TXO_8") (pintype "output"))
      (node (ref "U$2") (pin "P$20") (pinfunction "B1_P$20") (pintype "bidirectional"))
    )
    (net (code "74") (name "PSW") (class "Default")
      (node (ref "U2") (pin "21") (pinfunction "PSW_21") (pintype "bidirectional"))
      (node (ref "U3") (pin "21") (pinfunction "PSW_21") (pintype "bidirectional"))
    )
    (net (code "75") (name "PWRBTN#") (class "Default")
      (node (ref "R10") (pin "1") (pinfunction "1_1") (pintype "passive"))
      (node (ref "U2") (pin "17") (pinfunction "PWRBTN#_17") (pintype "bidirectional"))
      (node (ref "U3") (pin "17") (pinfunction "PWRBTN#_17") (pintype "bidirectional"))
    )
    (net (code "76") (name "RCVR_MODE") (class "Default")
      (node (ref "U2") (pin "31") (pinfunction "RCVR_MODE_31") (pintype "bidirectional"))
      (node (ref "U3") (pin "31") (pinfunction "RCVR_MODE_31") (pintype "bidirectional"))
    )
    (net (code "77") (name "RESET_OUT#") (class "Default")
      (node (ref "U2") (pin "36") (pinfunction "RESET_OUT#_36") (pintype "bidirectional"))
      (node (ref "U3") (pin "36") (pinfunction "RESET_OUT#_36") (pintype "bidirectional"))
    )
    (net (code "78") (name "USB_DN") (class "Default")
      (node (ref "U2") (pin "18") (pinfunction "USB_DN_18") (pintype "bidirectional"))
      (node (ref "U3") (pin "18") (pinfunction "USB_DN_18") (pintype "bidirectional"))
    )
    (net (code "79") (name "USB_DP") (class "Default")
      (node (ref "U2") (pin "16") (pinfunction "USB_DP_16") (pintype "bidirectional"))
      (node (ref "U3") (pin "16") (pinfunction "USB_DP_16") (pintype "bidirectional"))
    )
    (net (code "80") (name "USB_ID") (class "Default")
      (node (ref "U2") (pin "3") (pinfunction "USB_ID_3") (pintype "bidirectional"))
      (node (ref "U3") (pin "3") (pinfunction "USB_ID_3") (pintype "bidirectional"))
    )
    (net (code "81") (name "USB_VBUS") (class "Default")
      (node (ref "U2") (pin "20") (pinfunction "USB_VBUS_20") (pintype "bidirectional"))
      (node (ref "U3") (pin "20") (pinfunction "USB_VBUS_20") (pintype "bidirectional"))
    )
    (net (code "82") (name "VSYS") (class "Default")
      (node (ref "C8") (pin "1") (pinfunction "1_1") (pintype "passive"))
      (node (ref "C9") (pin "1") (pinfunction "1_1") (pintype "passive"))
      (node (ref "D3") (pin "A") (pinfunction "A_A") (pintype "passive"))
      (node (ref "L1") (pin "P$2") (pinfunction "2_P$2") (pintype "passive"))
      (node (ref "R7") (pin "2") (pinfunction "2_2") (pintype "passive"))
      (node (ref "R9") (pin "1") (pinfunction "1_1") (pintype "passive"))
      (node (ref "U2") (pin "2") (pinfunction "VSYS_2") (pintype "bidirectional"))
      (node (ref "U2") (pin "4") (pinfunction "VSYS_4") (pintype "bidirectional"))
      (node (ref "U2") (pin "6") (pinfunction "VSYS_6") (pintype "bidirectional"))
      (node (ref "U3") (pin "2") (pinfunction "VSYS_2") (pintype "bidirectional"))
      (node (ref "U3") (pin "4") (pinfunction "VSYS_4") (pintype "bidirectional"))
      (node (ref "U3") (pin "6") (pinfunction "VSYS_6") (pintype "bidirectional"))
      (node (ref "U5") (pin "1") (pinfunction "IN_1") (pintype "input"))
      (node (ref "U5") (pin "3") (pinfunction "EN_3") (pintype "input"))
    )
    (net (code "83") (name "V_BAT_BKUP") (class "Default")
      (node (ref "U2") (pin "23") (pinfunction "V_VAT_BKUP_23") (pintype "bidirectional"))
      (node (ref "U3") (pin "23") (pinfunction "V_VAT_BKUP_23") (pintype "bidirectional"))
    )
    (net (code "84") (name "unconnected-(JP3-D+-PadD+1)") (class "Default")
      (node (ref "JP3") (pin "D+1") (pinfunction "D+_D+1") (pintype "bidirectional"))
    )
    (net (code "85") (name "unconnected-(JP3-D--PadD-1)") (class "Default")
      (node (ref "JP3") (pin "D-1") (pinfunction "D-_D-1") (pintype "bidirectional"))
    )
    (net (code "86") (name "unconnected-(JP3-ID-PadID1)") (class "Default")
      (node (ref "JP3") (pin "ID1") (pinfunction "ID_ID1") (pintype "bidirectional"))
    )
    (net (code "87") (name "unconnected-(U$2-A8-PadP$10)") (class "Default")
      (node (ref "U$2") (pin "P$10") (pinfunction "A8_P$10") (pintype "bidirectional"))
    )
    (net (code "88") (name "unconnected-(U$2-B8-PadP$11)") (class "Default")
      (node (ref "U$2") (pin "P$11") (pinfunction "B8_P$11") (pintype "bidirectional"))
    )
    (net (code "89") (name "unconnected-(U5-BP-Pad4)") (class "Default")
      (node (ref "U5") (pin "4") (pinfunction "BP_4") (pintype "input"))
    )
  )
)
